# Audio.net
KiCad netlist of a schematic drawn in Altium Designer
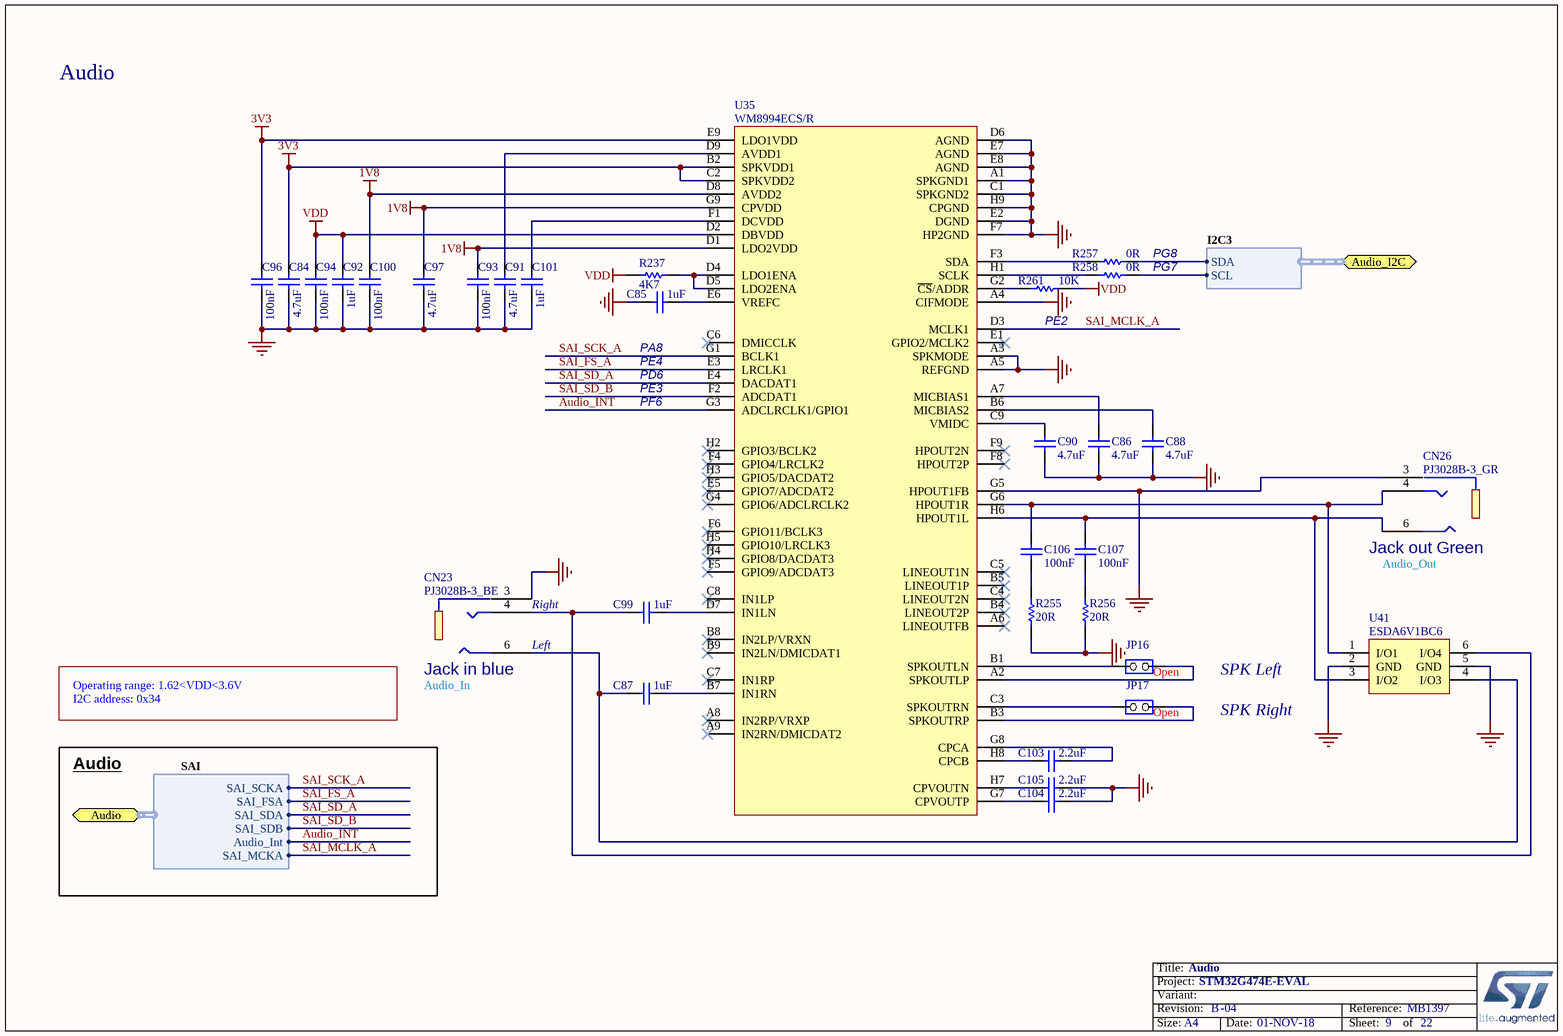
[diagram p0: Audio.SchDoc]

(export (version "E")
  (design (tool "Eeschema 10.0.6"))
  (components
    (comp (ref "C84")
      (value "4.7uF")
      (footprint "C0603")
      (description "Capacitor, MLCC, 4.7uF, 16V, X5R, 10%, 0603, T=0.8mm")
      (fields
        (field (name "INTERNAL_PART_NUMBER") "MCD-00009")
        (field (name "MANUFACTURER_PART_NUMBER") "CC0603KRX5R7BB475")
        (field (name "PROVIDED_BY") "SUBCO")
      )
      (libsource (lib "MCD_PARTS_database") (part "Capacitor"))
    )
    (comp (ref "C85")
      (value "1uF")
      (footprint "C0603")
      (description "Capacitor, MLCC, 1uF, 16V, X5R, 10%, 0603, T=0,8mm")
      (fields
        (field (name "INTERNAL_PART_NUMBER") "MCD-00010")
        (field (name "MANUFACTURER_PART_NUMBER") "CC0603KRX5R7BB105")
        (field (name "PROVIDED_BY") "SUBCO")
      )
      (libsource (lib "MCD_PARTS_database") (part "Capacitor"))
    )
    (comp (ref "C86")
      (value "4.7uF")
      (footprint "C0603")
      (description "Capacitor, MLCC, 4.7uF, 16V, X5R, 10%, 0603, T=0.8mm")
      (fields
        (field (name "INTERNAL_PART_NUMBER") "MCD-00009")
        (field (name "MANUFACTURER_PART_NUMBER") "CC0603KRX5R7BB475")
        (field (name "PROVIDED_BY") "SUBCO")
      )
      (libsource (lib "MCD_PARTS_database") (part "Capacitor"))
    )
    (comp (ref "C87")
      (value "1uF")
      (footprint "C0603")
      (description "Capacitor, MLCC, 1uF, 16V, X5R, 10%, 0603, T=0,8mm")
      (fields
        (field (name "INTERNAL_PART_NUMBER") "MCD-00010")
        (field (name "MANUFACTURER_PART_NUMBER") "CC0603KRX5R7BB105")
        (field (name "PROVIDED_BY") "SUBCO")
      )
      (libsource (lib "MCD_PARTS_database") (part "Capacitor"))
    )
    (comp (ref "C88")
      (value "4.7uF")
      (footprint "C0603")
      (description "Capacitor, MLCC, 4.7uF, 16V, X5R, 10%, 0603, T=0.8mm")
      (fields
        (field (name "INTERNAL_PART_NUMBER") "MCD-00009")
        (field (name "MANUFACTURER_PART_NUMBER") "CC0603KRX5R7BB475")
        (field (name "PROVIDED_BY") "SUBCO")
      )
      (libsource (lib "MCD_PARTS_database") (part "Capacitor"))
    )
    (comp (ref "C90")
      (value "4.7uF")
      (footprint "C0603")
      (description "Capacitor, MLCC, 4.7uF, 16V, X5R, 10%, 0603, T=0.8mm")
      (fields
        (field (name "INTERNAL_PART_NUMBER") "MCD-00009")
        (field (name "MANUFACTURER_PART_NUMBER") "CC0603KRX5R7BB475")
        (field (name "PROVIDED_BY") "SUBCO")
      )
      (libsource (lib "MCD_PARTS_database") (part "Capacitor"))
    )
    (comp (ref "C91")
      (value "4.7uF")
      (footprint "C0603")
      (description "Capacitor, MLCC, 4.7uF, 16V, X5R, 10%, 0603, T=0.8mm")
      (fields
        (field (name "INTERNAL_PART_NUMBER") "MCD-00009")
        (field (name "MANUFACTURER_PART_NUMBER") "CC0603KRX5R7BB475")
        (field (name "PROVIDED_BY") "SUBCO")
      )
      (libsource (lib "MCD_PARTS_database") (part "Capacitor"))
    )
    (comp (ref "C92")
      (value "1uF")
      (footprint "C0603")
      (description "Capacitor, MLCC, 1uF, 16V, X5R, 10%, 0603, T=0,8mm")
      (fields
        (field (name "INTERNAL_PART_NUMBER") "MCD-00010")
        (field (name "MANUFACTURER_PART_NUMBER") "CC0603KRX5R7BB105")
        (field (name "PROVIDED_BY") "SUBCO")
      )
      (libsource (lib "MCD_PARTS_database") (part "Capacitor"))
    )
    (comp (ref "C93")
      (value "100nF")
      (footprint "C0402")
      (description "Capacitor, MLCC, 100nF, 16V, X7R, 10%, 0402, T=0.5mm")
      (fields
        (field (name "INTERNAL_PART_NUMBER") "MCD-00006")
        (field (name "MANUFACTURER_PART_NUMBER") "CC0402KRX7R7BB104")
        (field (name "PROVIDED_BY") "SUBCO")
      )
      (libsource (lib "MCD_PARTS_database") (part "Capacitor"))
    )
    (comp (ref "C94")
      (value "100nF")
      (footprint "C0402")
      (description "Capacitor, MLCC, 100nF, 16V, X7R, 10%, 0402, T=0.5mm")
      (fields
        (field (name "INTERNAL_PART_NUMBER") "MCD-00006")
        (field (name "MANUFACTURER_PART_NUMBER") "CC0402KRX7R7BB104")
        (field (name "PROVIDED_BY") "SUBCO")
      )
      (libsource (lib "MCD_PARTS_database") (part "Capacitor"))
    )
    (comp (ref "C96")
      (value "100nF")
      (footprint "C0402")
      (description "Capacitor, MLCC, 100nF, 16V, X7R, 10%, 0402, T=0.5mm")
      (fields
        (field (name "INTERNAL_PART_NUMBER") "MCD-00006")
        (field (name "MANUFACTURER_PART_NUMBER") "CC0402KRX7R7BB104")
        (field (name "PROVIDED_BY") "SUBCO")
      )
      (libsource (lib "MCD_PARTS_database") (part "Capacitor"))
    )
    (comp (ref "C97")
      (value "4.7uF")
      (footprint "C0603")
      (description "Capacitor, MLCC, 4.7uF, 16V, X5R, 10%, 0603, T=0.8mm")
      (fields
        (field (name "INTERNAL_PART_NUMBER") "MCD-00009")
        (field (name "MANUFACTURER_PART_NUMBER") "CC0603KRX5R7BB475")
        (field (name "PROVIDED_BY") "SUBCO")
      )
      (libsource (lib "MCD_PARTS_database") (part "Capacitor"))
    )
    (comp (ref "C99")
      (value "1uF")
      (footprint "C0603")
      (description "Capacitor, MLCC, 1uF, 16V, X5R, 10%, 0603, T=0,8mm")
      (fields
        (field (name "INTERNAL_PART_NUMBER") "MCD-00010")
        (field (name "MANUFACTURER_PART_NUMBER") "CC0603KRX5R7BB105")
        (field (name "PROVIDED_BY") "SUBCO")
      )
      (libsource (lib "MCD_PARTS_database") (part "Capacitor"))
    )
    (comp (ref "C100")
      (value "100nF")
      (footprint "C0402")
      (description "Capacitor, MLCC, 100nF, 16V, X7R, 10%, 0402, T=0.5mm")
      (fields
        (field (name "INTERNAL_PART_NUMBER") "MCD-00006")
        (field (name "MANUFACTURER_PART_NUMBER") "CC0402KRX7R7BB104")
        (field (name "PROVIDED_BY") "SUBCO")
      )
      (libsource (lib "MCD_PARTS_database") (part "Capacitor"))
    )
    (comp (ref "C101")
      (value "1uF")
      (footprint "C0603")
      (description "Capacitor, MLCC, 1uF, 16V, X5R, 10%, 0603, T=0,8mm")
      (fields
        (field (name "INTERNAL_PART_NUMBER") "MCD-00010")
        (field (name "MANUFACTURER_PART_NUMBER") "CC0603KRX5R7BB105")
        (field (name "PROVIDED_BY") "SUBCO")
      )
      (libsource (lib "MCD_PARTS_database") (part "Capacitor"))
    )
    (comp (ref "C103")
      (value "2.2uF")
      (footprint "C0603")
      (description "Capacitor, MLCC, 2.2uF, 10V, X5R, 10%, 0603, T=0,8mm")
      (fields
        (field (name "INTERNAL_PART_NUMBER") "MCD-00012")
        (field (name "MANUFACTURER_PART_NUMBER") "CC0603KRX5R6BB225")
        (field (name "PROVIDED_BY") "SUBCO")
      )
      (libsource (lib "MCD_PARTS_database") (part "Capacitor"))
    )
    (comp (ref "C104")
      (value "2.2uF")
      (footprint "C0603")
      (description "Capacitor, MLCC, 2.2uF, 10V, X5R, 10%, 0603, T=0,8mm")
      (fields
        (field (name "INTERNAL_PART_NUMBER") "MCD-00012")
        (field (name "MANUFACTURER_PART_NUMBER") "CC0603KRX5R6BB225")
        (field (name "PROVIDED_BY") "SUBCO")
      )
      (libsource (lib "MCD_PARTS_database") (part "Capacitor"))
    )
    (comp (ref "C105")
      (value "2.2uF")
      (footprint "C0603")
      (description "Capacitor, MLCC, 2.2uF, 10V, X5R, 10%, 0603, T=0,8mm")
      (fields
        (field (name "INTERNAL_PART_NUMBER") "MCD-00012")
        (field (name "MANUFACTURER_PART_NUMBER") "CC0603KRX5R6BB225")
        (field (name "PROVIDED_BY") "SUBCO")
      )
      (libsource (lib "MCD_PARTS_database") (part "Capacitor"))
    )
    (comp (ref "C106")
      (value "100nF")
      (footprint "C0402")
      (description "Capacitor, MLCC, 100nF, 16V, X7R, 10%, 0402, T=0.5mm")
      (fields
        (field (name "INTERNAL_PART_NUMBER") "MCD-00006")
        (field (name "MANUFACTURER_PART_NUMBER") "CC0402KRX7R7BB104")
        (field (name "PROVIDED_BY") "SUBCO")
      )
      (libsource (lib "MCD_PARTS_database") (part "Capacitor"))
    )
    (comp (ref "C107")
      (value "100nF")
      (footprint "C0402")
      (description "Capacitor, MLCC, 100nF, 16V, X7R, 10%, 0402, T=0.5mm")
      (fields
        (field (name "INTERNAL_PART_NUMBER") "MCD-00006")
        (field (name "MANUFACTURER_PART_NUMBER") "CC0402KRX7R7BB104")
        (field (name "PROVIDED_BY") "SUBCO")
      )
      (libsource (lib "MCD_PARTS_database") (part "Capacitor"))
    )
    (comp (ref "CN23")
      (value "PJ3028B-3_BE")
      (footprint "CON_PHONE-JACK-3P5_HY_PJ3028B")
      (description "Connector Jack socket Stereo 3.5mm, 3 pins, RA, SMT, Blue (Line input)")
      (fields
        (field (name "INTERNAL_PART_NUMBER") "MCD-00682")
        (field (name "MANUFACTURER") "QIAOD")
        (field (name "PROVIDED_BY") "SUBCO")
      )
      (libsource (lib "") (part "Jack_PJ3028B-3_3P_1"))
    )
    (comp (ref "CN26")
      (value "PJ3028B-3_GR")
      (footprint "CON_PHONE-JACK-3P5_HY_PJ3028B")
      (description "Connector Jack socket Stereo 3.5mm, 3 pins, RA, SMT, Green (Line output)")
      (fields
        (field (name "INTERNAL_PART_NUMBER") "MCD-00018")
        (field (name "MANUFACTURER") "QIAOD")
        (field (name "PROVIDED_BY") "SUBCO")
      )
      (libsource (lib "MCD_PARTS_database") (part "Jack_PJ3028B-3_3P"))
    )
    (comp (ref "JP16")
      (value "Jumper_Header 2x1")
      (footprint "CON_SAMTEC_TSW-102-07-G-S")
      (description "Header, 2x1, 2,54mm, VR, TH, Height 5.84mm/2.54mm")
      (fields
        (field (name "INTERNAL_PART_NUMBER") "MCD-00045")
        (field (name "MANUFACTURER_PART_NUMBER") "TSW-102-07-x-S")
        (field (name "PROVIDED_BY") "SUBCO")
      )
      (libsource (lib "MCD_PARTS_database") (part "Jumper_Header 2x1"))
    )
    (comp (ref "JP17")
      (value "Jumper_Header 2x1")
      (footprint "CON_SAMTEC_TSW-102-07-G-S")
      (description "Header, 2x1, 2,54mm, VR, TH, Height 5.84mm/2.54mm")
      (fields
        (field (name "INTERNAL_PART_NUMBER") "MCD-00045")
        (field (name "MANUFACTURER_PART_NUMBER") "TSW-102-07-x-S")
        (field (name "PROVIDED_BY") "SUBCO")
      )
      (libsource (lib "MCD_PARTS_database") (part "Jumper_Header 2x1"))
    )
    (comp (ref "R237")
      (value "4K7")
      (footprint "R0402")
      (description "Resistor,4K7,0402,1%,1/16W")
      (fields
        (field (name "INTERNAL_PART_NUMBER") "MCD-00065")
        (field (name "MANUFACTURER_PART_NUMBER") "RC0402FR-074K7L")
        (field (name "PROVIDED_BY") "SUBCO")
      )
      (libsource (lib "MCD_PARTS_database") (part "Resistor"))
    )
    (comp (ref "R255")
      (value "20R")
      (footprint "R0603")
      (description "Resistor,20R,0603,1%,1/10W")
      (fields
        (field (name "INTERNAL_PART_NUMBER") "MCD-00345")
        (field (name "MANUFACTURER_PART_NUMBER") "RC0603FR-0720RL")
        (field (name "PROVIDED_BY") "SUBCO")
      )
      (libsource (lib "MCD_PARTS_database") (part "Resistor"))
    )
    (comp (ref "R256")
      (value "20R")
      (footprint "R0603")
      (description "Resistor,20R,0603,1%,1/10W")
      (fields
        (field (name "INTERNAL_PART_NUMBER") "MCD-00345")
        (field (name "MANUFACTURER_PART_NUMBER") "RC0603FR-0720RL")
        (field (name "PROVIDED_BY") "SUBCO")
      )
      (libsource (lib "MCD_PARTS_database") (part "Resistor"))
    )
    (comp (ref "R257")
      (value "0R")
      (footprint "R0603")
      (description "Resistor,0R,0603,5%,1/10W")
      (fields
        (field (name "INTERNAL_PART_NUMBER") "MCD-00056")
        (field (name "MANUFACTURER_PART_NUMBER") "RC0603JR-070RL")
        (field (name "PROVIDED_BY") "SUBCO")
      )
      (libsource (lib "MCD_PARTS_database") (part "Resistor"))
    )
    (comp (ref "R258")
      (value "0R")
      (footprint "R0603")
      (description "Resistor,0R,0603,5%,1/10W")
      (fields
        (field (name "INTERNAL_PART_NUMBER") "MCD-00056")
        (field (name "MANUFACTURER_PART_NUMBER") "RC0603JR-070RL")
        (field (name "PROVIDED_BY") "SUBCO")
      )
      (libsource (lib "MCD_PARTS_database") (part "Resistor"))
    )
    (comp (ref "R261")
      (value "10K")
      (footprint "R0402")
      (description "Resistor,10K,0402,1%,1/16W")
      (fields
        (field (name "INTERNAL_PART_NUMBER") "MCD-00053")
        (field (name "MANUFACTURER_PART_NUMBER") "RC0402FR-0710KL")
        (field (name "PROVIDED_BY") "SUBCO")
      )
      (libsource (lib "MCD_PARTS_database") (part "Resistor"))
    )
    (comp (ref "U35")
      (value "WM8994ECS/R")
      (footprint "ICC_W-CSP-BGA72_4P511X4P023_P050")
      (description "Multi-Channel Audio Hub CODEC for Smartphones")
      (fields
        (field (name "INTERNAL_PART_NUMBER") "MCD-00079")
        (field (name "MANUFACTURER") "CIRRUS LOGIC")
        (field (name "PROVIDED_BY") "SUBCO")
      )
      (libsource (lib "MCD_PARTS_database") (part "WM8994ECS/R"))
    )
    (comp (ref "U41")
      (value "ESDA6V1BC6")
      (footprint "ESD_SOT23-6L")
      (description "Quad Bidir ESD protection")
      (fields
        (field (name "INTERNAL_PART_NUMBER") "MCD-00247")
        (field (name "MANUFACTURER") "STMICROELECTRONICS")
        (field (name "PROVIDED_BY") "SUBCO with ST control")
      )
      (libsource (lib "MCD_PARTS_database") (part "ESDA6V1BC6"))
    )
  )
  (nets
    (net (code "3") (name "/Audio_INT") (class "Default")
      (node (ref "U35") (pin "G3") (pinfunction "ADCLRCLK1/GPIO1_G3") (pintype "passive"))
    )
    (net (code "4") (name "/SAI_FS_A") (class "Default")
      (node (ref "U35") (pin "E3") (pinfunction "LRCLK1_E3") (pintype "passive"))
    )
    (net (code "5") (name "/SAI_MCLK_A") (class "Default")
      (node (ref "U35") (pin "D3") (pinfunction "MCLK1_D3") (pintype "passive"))
    )
    (net (code "6") (name "/SAI_SCK_A") (class "Default")
      (node (ref "U35") (pin "G1") (pinfunction "BCLK1_G1") (pintype "passive"))
    )
    (net (code "7") (name "/SAI_SD_A") (class "Default")
      (node (ref "U35") (pin "E4") (pinfunction "DACDAT1_E4") (pintype "passive"))
    )
    (net (code "8") (name "/SAI_SD_B") (class "Default")
      (node (ref "U35") (pin "F2") (pinfunction "ADCDAT1_F2") (pintype "passive"))
    )
    (net (code "9") (name "/SCL") (class "Default")
      (node (ref "R258") (pin "2") (pinfunction "2_2") (pintype "passive"))
    )
    (net (code "10") (name "/SDA") (class "Default")
      (node (ref "R257") (pin "2") (pinfunction "2_2") (pintype "passive"))
    )
    (net (code "13") (name "1V8") (class "Default")
      (node (ref "C100") (pin "1") (pinfunction "1_1") (pintype "passive"))
      (node (ref "C93") (pin "1") (pinfunction "1_1") (pintype "passive"))
      (node (ref "C97") (pin "2") (pinfunction "2_2") (pintype "passive"))
      (node (ref "U35") (pin "D1") (pinfunction "LDO2VDD_D1") (pintype "passive"))
      (node (ref "U35") (pin "D8") (pinfunction "AVDD2_D8") (pintype "passive"))
      (node (ref "U35") (pin "G9") (pinfunction "CPVDD_G9") (pintype "passive"))
    )
    (net (code "14") (name "3V3") (class "Default")
      (node (ref "C84") (pin "2") (pinfunction "2_2") (pintype "passive"))
      (node (ref "C96") (pin "1") (pinfunction "1_1") (pintype "passive"))
      (node (ref "U35") (pin "B2") (pinfunction "SPKVDD1_B2") (pintype "passive"))
      (node (ref "U35") (pin "C2") (pinfunction "SPKVDD2_C2") (pintype "passive"))
      (node (ref "U35") (pin "E9") (pinfunction "LDO1VDD_E9") (pintype "passive"))
    )
    (net (code "15") (name "GND") (class "Default")
      (node (ref "C100") (pin "2") (pinfunction "2_2") (pintype "passive"))
      (node (ref "C101") (pin "1") (pinfunction "1_1") (pintype "passive"))
      (node (ref "C104") (pin "1") (pinfunction "1_1") (pintype "passive"))
      (node (ref "C105") (pin "1") (pinfunction "1_1") (pintype "passive"))
      (node (ref "C84") (pin "1") (pinfunction "1_1") (pintype "passive"))
      (node (ref "C85") (pin "2") (pinfunction "2_2") (pintype "passive"))
      (node (ref "C86") (pin "1") (pinfunction "1_1") (pintype "passive"))
      (node (ref "C88") (pin "1") (pinfunction "1_1") (pintype "passive"))
      (node (ref "C90") (pin "1") (pinfunction "1_1") (pintype "passive"))
      (node (ref "C91") (pin "1") (pinfunction "1_1") (pintype "passive"))
      (node (ref "C92") (pin "1") (pinfunction "1_1") (pintype "passive"))
      (node (ref "C93") (pin "2") (pinfunction "2_2") (pintype "passive"))
      (node (ref "C94") (pin "2") (pinfunction "2_2") (pintype "passive"))
      (node (ref "C96") (pin "2") (pinfunction "2_2") (pintype "passive"))
      (node (ref "C97") (pin "1") (pinfunction "1_1") (pintype "passive"))
      (node (ref "CN23") (pin "3") (pintype "passive"))
      (node (ref "CN26") (pin "3") (pintype "passive"))
      (node (ref "R255") (pin "1") (pinfunction "1_1") (pintype "passive"))
      (node (ref "R256") (pin "1") (pinfunction "1_1") (pintype "passive"))
      (node (ref "U35") (pin "A1") (pinfunction "SPKGND1_A1") (pintype "passive"))
      (node (ref "U35") (pin "A3") (pinfunction "SPKMODE_A3") (pintype "passive"))
      (node (ref "U35") (pin "A4") (pinfunction "CIFMODE_A4") (pintype "passive"))
      (node (ref "U35") (pin "A5") (pinfunction "REFGND_A5") (pintype "passive"))
      (node (ref "U35") (pin "C1") (pinfunction "SPKGND2_C1") (pintype "passive"))
      (node (ref "U35") (pin "D6") (pinfunction "AGND_D6") (pintype "passive"))
      (node (ref "U35") (pin "E2") (pinfunction "DGND_E2") (pintype "passive"))
      (node (ref "U35") (pin "E7") (pinfunction "AGND_E7") (pintype "passive"))
      (node (ref "U35") (pin "E8") (pinfunction "AGND_E8") (pintype "passive"))
      (node (ref "U35") (pin "F7") (pinfunction "HP2GND_F7") (pintype "passive"))
      (node (ref "U35") (pin "G5") (pinfunction "HPOUT1FB_G5") (pintype "passive"))
      (node (ref "U35") (pin "H9") (pinfunction "CPGND_H9") (pintype "passive"))
      (node (ref "U41") (pin "2") (pinfunction "GND_2") (pintype "passive"))
      (node (ref "U41") (pin "5") (pinfunction "GND_5") (pintype "passive"))
    )
    (net (code "16") (name "Net-(C106-Pad2)") (class "Default")
      (node (ref "C106") (pin "2") (pinfunction "2_2") (pintype "passive"))
      (node (ref "R255") (pin "2") (pinfunction "2_2") (pintype "passive"))
    )
    (net (code "17") (name "Net-(C107-Pad2)") (class "Default")
      (node (ref "C107") (pin "2") (pinfunction "2_2") (pintype "passive"))
      (node (ref "R256") (pin "2") (pinfunction "2_2") (pintype "passive"))
    )
    (net (code "18") (name "Net-(JP16-COMMON)") (class "Default")
      (node (ref "JP16") (pin "1") (pinfunction "COMMON_1") (pintype "passive"))
      (node (ref "U35") (pin "A2") (pinfunction "SPKOUTLP_A2") (pintype "passive"))
    )
    (net (code "19") (name "Net-(JP16-NO)") (class "Default")
      (node (ref "JP16") (pin "2") (pinfunction "NO_2") (pintype "passive"))
      (node (ref "U35") (pin "B1") (pinfunction "SPKOUTLN_B1") (pintype "passive"))
    )
    (net (code "20") (name "Net-(JP17-COMMON)") (class "Default")
      (node (ref "JP17") (pin "1") (pinfunction "COMMON_1") (pintype "passive"))
      (node (ref "U35") (pin "B3") (pinfunction "SPKOUTRP_B3") (pintype "passive"))
    )
    (net (code "21") (name "Net-(JP17-NO)") (class "Default")
      (node (ref "JP17") (pin "2") (pinfunction "NO_2") (pintype "passive"))
      (node (ref "U35") (pin "C3") (pinfunction "SPKOUTRN_C3") (pintype "passive"))
    )
    (net (code "22") (name "Net-(U35-AVDD1)") (class "Default")
      (node (ref "C91") (pin "2") (pinfunction "2_2") (pintype "passive"))
      (node (ref "U35") (pin "D9") (pinfunction "AVDD1_D9") (pintype "passive"))
    )
    (net (code "23") (name "Net-(U35-CPCA)") (class "Default")
      (node (ref "C103") (pin "1") (pinfunction "1_1") (pintype "passive"))
      (node (ref "U35") (pin "G8") (pinfunction "CPCA_G8") (pintype "passive"))
    )
    (net (code "24") (name "Net-(U35-CPCB)") (class "Default")
      (node (ref "C103") (pin "2") (pinfunction "2_2") (pintype "passive"))
      (node (ref "U35") (pin "H8") (pinfunction "CPCB_H8") (pintype "passive"))
    )
    (net (code "25") (name "Net-(U35-CPVOUTN)") (class "Default")
      (node (ref "C105") (pin "2") (pinfunction "2_2") (pintype "passive"))
      (node (ref "U35") (pin "H7") (pinfunction "CPVOUTN_H7") (pintype "passive"))
    )
    (net (code "26") (name "Net-(U35-CPVOUTP)") (class "Default")
      (node (ref "C104") (pin "2") (pinfunction "2_2") (pintype "passive"))
      (node (ref "U35") (pin "G7") (pinfunction "CPVOUTP_G7") (pintype "passive"))
    )
    (net (code "27") (name "Net-(U35-DCVDD)") (class "Default")
      (node (ref "C101") (pin "2") (pinfunction "2_2") (pintype "passive"))
      (node (ref "U35") (pin "F1") (pinfunction "DCVDD_F1") (pintype "passive"))
    )
    (net (code "28") (name "Net-(U35-HPOUT1L)") (class "Default")
      (node (ref "C107") (pin "1") (pinfunction "1_1") (pintype "passive"))
      (node (ref "CN26") (pin "6") (pintype "passive"))
      (node (ref "U35") (pin "H6") (pinfunction "HPOUT1L_H6") (pintype "passive"))
      (node (ref "U41") (pin "3") (pinfunction "I/O2_3") (pintype "passive"))
    )
    (net (code "29") (name "Net-(U35-HPOUT1R)") (class "Default")
      (node (ref "C106") (pin "1") (pinfunction "1_1") (pintype "passive"))
      (node (ref "CN26") (pin "4") (pintype "passive"))
      (node (ref "U35") (pin "G6") (pinfunction "HPOUT1R_G6") (pintype "passive"))
      (node (ref "U41") (pin "1") (pinfunction "I/O1_1") (pintype "passive"))
    )
    (net (code "30") (name "Net-(U35-IN1LN)") (class "Default")
      (node (ref "C99") (pin "1") (pinfunction "1_1") (pintype "passive"))
      (node (ref "U35") (pin "D7") (pinfunction "IN1LN_D7") (pintype "passive"))
    )
    (net (code "31") (name "Net-(U35-IN1RN)") (class "Default")
      (node (ref "C87") (pin "1") (pinfunction "1_1") (pintype "passive"))
      (node (ref "U35") (pin "B7") (pinfunction "IN1RN_B7") (pintype "passive"))
    )
    (net (code "32") (name "Net-(U35-LDO1ENA)") (class "Default")
      (node (ref "R237") (pin "2") (pinfunction "2_2") (pintype "passive"))
      (node (ref "U35") (pin "D4") (pinfunction "LDO1ENA_D4") (pintype "passive"))
      (node (ref "U35") (pin "D5") (pinfunction "LDO2ENA_D5") (pintype "passive"))
    )
    (net (code "33") (name "Net-(U35-MICBIAS1)") (class "Default")
      (node (ref "C86") (pin "2") (pinfunction "2_2") (pintype "passive"))
      (node (ref "U35") (pin "A7") (pinfunction "MICBIAS1_A7") (pintype "passive"))
    )
    (net (code "34") (name "Net-(U35-MICBIAS2)") (class "Default")
      (node (ref "C88") (pin "2") (pinfunction "2_2") (pintype "passive"))
      (node (ref "U35") (pin "B6") (pinfunction "MICBIAS2_B6") (pintype "passive"))
    )
    (net (code "35") (name "Net-(U35-SCLK)") (class "Default")
      (node (ref "R258") (pin "1") (pinfunction "1_1") (pintype "passive"))
      (node (ref "U35") (pin "H1") (pinfunction "SCLK_H1") (pintype "passive"))
    )
    (net (code "36") (name "Net-(U35-SDA)") (class "Default")
      (node (ref "R257") (pin "1") (pinfunction "1_1") (pintype "passive"))
      (node (ref "U35") (pin "F3") (pinfunction "SDA_F3") (pintype "passive"))
    )
    (net (code "37") (name "Net-(U35-VMIDC)") (class "Default")
      (node (ref "C90") (pin "2") (pinfunction "2_2") (pintype "passive"))
      (node (ref "U35") (pin "C9") (pinfunction "VMIDC_C9") (pintype "passive"))
    )
    (net (code "38") (name "Net-(U35-VREFC)") (class "Default")
      (node (ref "C85") (pin "1") (pinfunction "1_1") (pintype "passive"))
      (node (ref "U35") (pin "E6") (pinfunction "VREFC_E6") (pintype "passive"))
    )
    (net (code "39") (name "Net-(U35-~{CS}{slash}ADDR)") (class "Default")
      (node (ref "R261") (pin "2") (pinfunction "2_2") (pintype "passive"))
      (node (ref "U35") (pin "G2") (pinfunction "~{CS}/ADDR_G2") (pintype "passive"))
    )
    (net (code "40") (name "Net-(U41-I{slash}O3)") (class "Default")
      (node (ref "C87") (pin "2") (pinfunction "2_2") (pintype "passive"))
      (node (ref "CN23") (pin "6") (pintype "passive"))
      (node (ref "U41") (pin "4") (pinfunction "I/O3_4") (pintype "passive"))
    )
    (net (code "41") (name "Net-(U41-I{slash}O4)") (class "Default")
      (node (ref "C99") (pin "2") (pinfunction "2_2") (pintype "passive"))
      (node (ref "CN23") (pin "4") (pintype "passive"))
      (node (ref "U41") (pin "6") (pinfunction "I/O4_6") (pintype "passive"))
    )
    (net (code "42") (name "VDD") (class "Default")
      (node (ref "C92") (pin "2") (pinfunction "2_2") (pintype "passive"))
      (node (ref "C94") (pin "1") (pinfunction "1_1") (pintype "passive"))
      (node (ref "R237") (pin "1") (pinfunction "1_1") (pintype "passive"))
      (node (ref "R261") (pin "1") (pinfunction "1_1") (pintype "passive"))
      (node (ref "U35") (pin "D2") (pinfunction "DBVDD_D2") (pintype "passive"))
    )
    (net (code "43") (name "unconnected-(U35-DMICCLK-PadC6)") (class "Default")
      (node (ref "U35") (pin "C6") (pinfunction "DMICCLK_C6") (pintype "passive+no_connect"))
    )
    (net (code "44") (name "unconnected-(U35-GPIO2{slash}MCLK2-PadE1)") (class "Default")
      (node (ref "U35") (pin "E1") (pinfunction "GPIO2/MCLK2_E1") (pintype "passive+no_connect"))
    )
    (net (code "45") (name "unconnected-(U35-GPIO3{slash}BCLK2-PadH2)") (class "Default")
      (node (ref "U35") (pin "H2") (pinfunction "GPIO3/BCLK2_H2") (pintype "passive+no_connect"))
    )
    (net (code "46") (name "unconnected-(U35-GPIO4{slash}LRCLK2-PadF4)") (class "Default")
      (node (ref "U35") (pin "F4") (pinfunction "GPIO4/LRCLK2_F4") (pintype "passive+no_connect"))
    )
    (net (code "47") (name "unconnected-(U35-GPIO5{slash}DACDAT2-PadH3)") (class "Default")
      (node (ref "U35") (pin "H3") (pinfunction "GPIO5/DACDAT2_H3") (pintype "passive+no_connect"))
    )
    (net (code "48") (name "unconnected-(U35-GPIO6{slash}ADCLRCLK2-PadG4)") (class "Default")
      (node (ref "U35") (pin "G4") (pinfunction "GPIO6/ADCLRCLK2_G4") (pintype "passive+no_connect"))
    )
    (net (code "49") (name "unconnected-(U35-GPIO7{slash}ADCDAT2-PadE5)") (class "Default")
      (node (ref "U35") (pin "E5") (pinfunction "GPIO7/ADCDAT2_E5") (pintype "passive+no_connect"))
    )
    (net (code "50") (name "unconnected-(U35-GPIO8{slash}DACDAT3-PadH4)") (class "Default")
      (node (ref "U35") (pin "H4") (pinfunction "GPIO8/DACDAT3_H4") (pintype "passive+no_connect"))
    )
    (net (code "51") (name "unconnected-(U35-GPIO9{slash}ADCDAT3-PadF5)") (class "Default")
      (node (ref "U35") (pin "F5") (pinfunction "GPIO9/ADCDAT3_F5") (pintype "passive+no_connect"))
    )
    (net (code "52") (name "unconnected-(U35-GPIO10{slash}LRCLK3-PadH5)") (class "Default")
      (node (ref "U35") (pin "H5") (pinfunction "GPIO10/LRCLK3_H5") (pintype "passive+no_connect"))
    )
    (net (code "53") (name "unconnected-(U35-GPIO11{slash}BCLK3-PadF6)") (class "Default")
      (node (ref "U35") (pin "F6") (pinfunction "GPIO11/BCLK3_F6") (pintype "passive+no_connect"))
    )
    (net (code "54") (name "unconnected-(U35-HPOUT2N-PadF9)") (class "Default")
      (node (ref "U35") (pin "F9") (pinfunction "HPOUT2N_F9") (pintype "passive+no_connect"))
    )
    (net (code "55") (name "unconnected-(U35-HPOUT2P-PadF8)") (class "Default")
      (node (ref "U35") (pin "F8") (pinfunction "HPOUT2P_F8") (pintype "passive+no_connect"))
    )
    (net (code "56") (name "unconnected-(U35-IN1LP-PadC8)") (class "Default")
      (node (ref "U35") (pin "C8") (pinfunction "IN1LP_C8") (pintype "passive+no_connect"))
    )
    (net (code "57") (name "unconnected-(U35-IN1RP-PadC7)") (class "Default")
      (node (ref "U35") (pin "C7") (pinfunction "IN1RP_C7") (pintype "passive+no_connect"))
    )
    (net (code "58") (name "unconnected-(U35-IN2LN{slash}DMICDAT1-PadB9)") (class "Default")
      (node (ref "U35") (pin "B9") (pinfunction "IN2LN/DMICDAT1_B9") (pintype "passive+no_connect"))
    )
    (net (code "59") (name "unconnected-(U35-IN2LP{slash}VRXN-PadB8)") (class "Default")
      (node (ref "U35") (pin "B8") (pinfunction "IN2LP/VRXN_B8") (pintype "passive+no_connect"))
    )
    (net (code "60") (name "unconnected-(U35-IN2RN{slash}DMICDAT2-PadA9)") (class "Default")
      (node (ref "U35") (pin "A9") (pinfunction "IN2RN/DMICDAT2_A9") (pintype "passive+no_connect"))
    )
    (net (code "61") (name "unconnected-(U35-IN2RP{slash}VRXP-PadA8)") (class "Default")
      (node (ref "U35") (pin "A8") (pinfunction "IN2RP/VRXP_A8") (pintype "passive+no_connect"))
    )
    (net (code "62") (name "unconnected-(U35-LINEOUT1N-PadC5)") (class "Default")
      (node (ref "U35") (pin "C5") (pinfunction "LINEOUT1N_C5") (pintype "passive+no_connect"))
    )
    (net (code "63") (name "unconnected-(U35-LINEOUT1P-PadB5)") (class "Default")
      (node (ref "U35") (pin "B5") (pinfunction "LINEOUT1P_B5") (pintype "passive+no_connect"))
    )
    (net (code "64") (name "unconnected-(U35-LINEOUT2N-PadC4)") (class "Default")
      (node (ref "U35") (pin "C4") (pinfunction "LINEOUT2N_C4") (pintype "passive+no_connect"))
    )
    (net (code "65") (name "unconnected-(U35-LINEOUT2P-PadB4)") (class "Default")
      (node (ref "U35") (pin "B4") (pinfunction "LINEOUT2P_B4") (pintype "passive+no_connect"))
    )
    (net (code "66") (name "unconnected-(U35-LINEOUTFB-PadA6)") (class "Default")
      (node (ref "U35") (pin "A6") (pinfunction "LINEOUTFB_A6") (pintype "passive+no_connect"))
    )
  )
)
